# extruderControllerv03.net
KiCad netlist of a schematic drawn in EAGLE
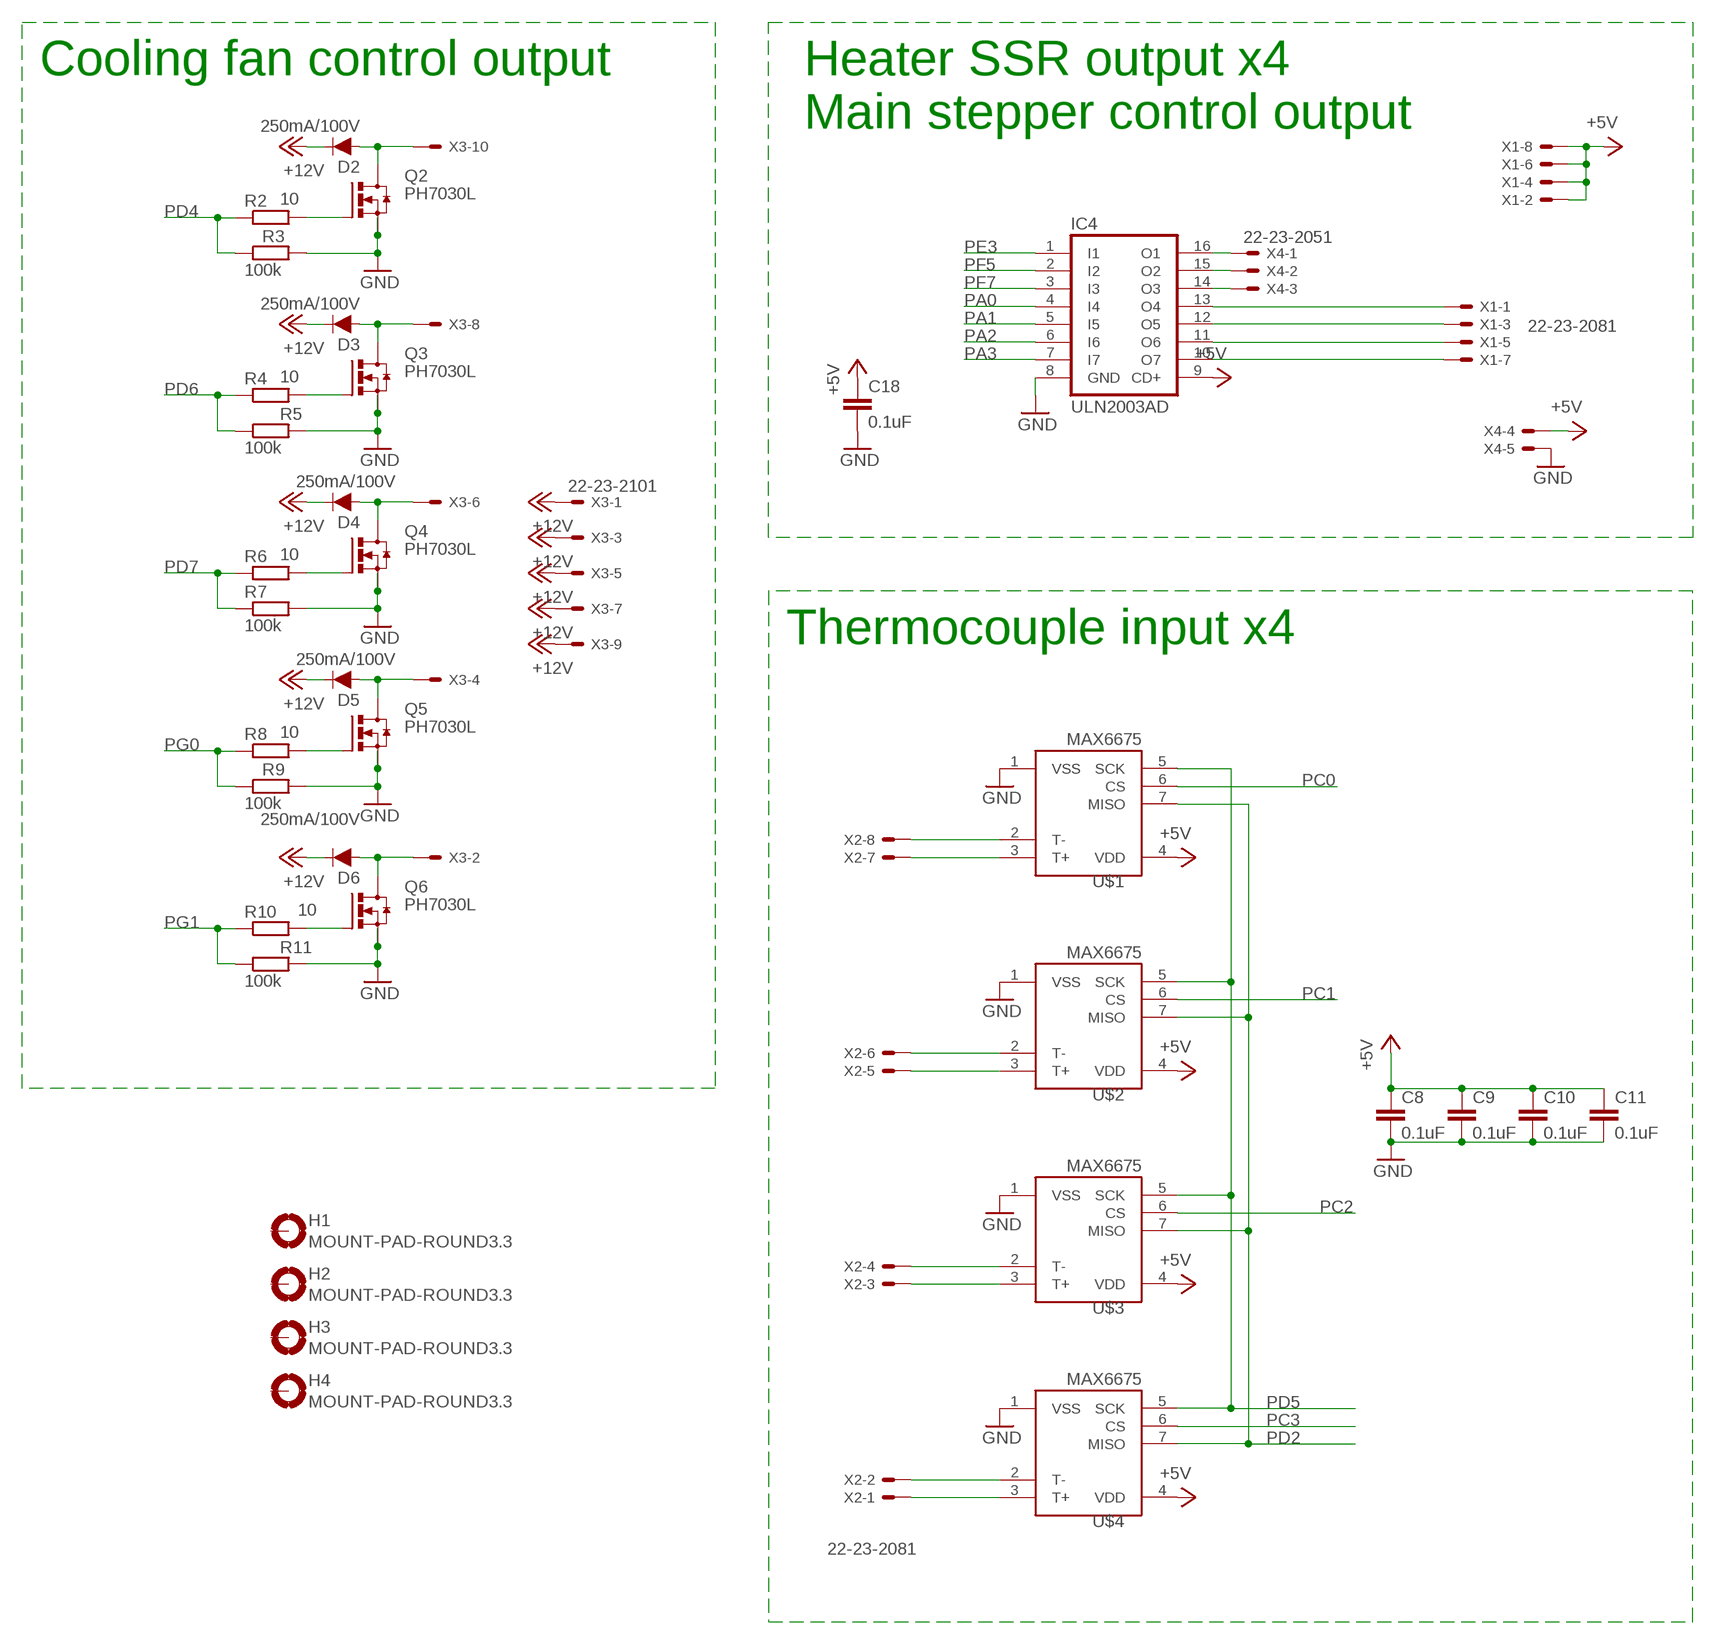
[diagram p0: schematic, sheet 1, part 1 of 2]
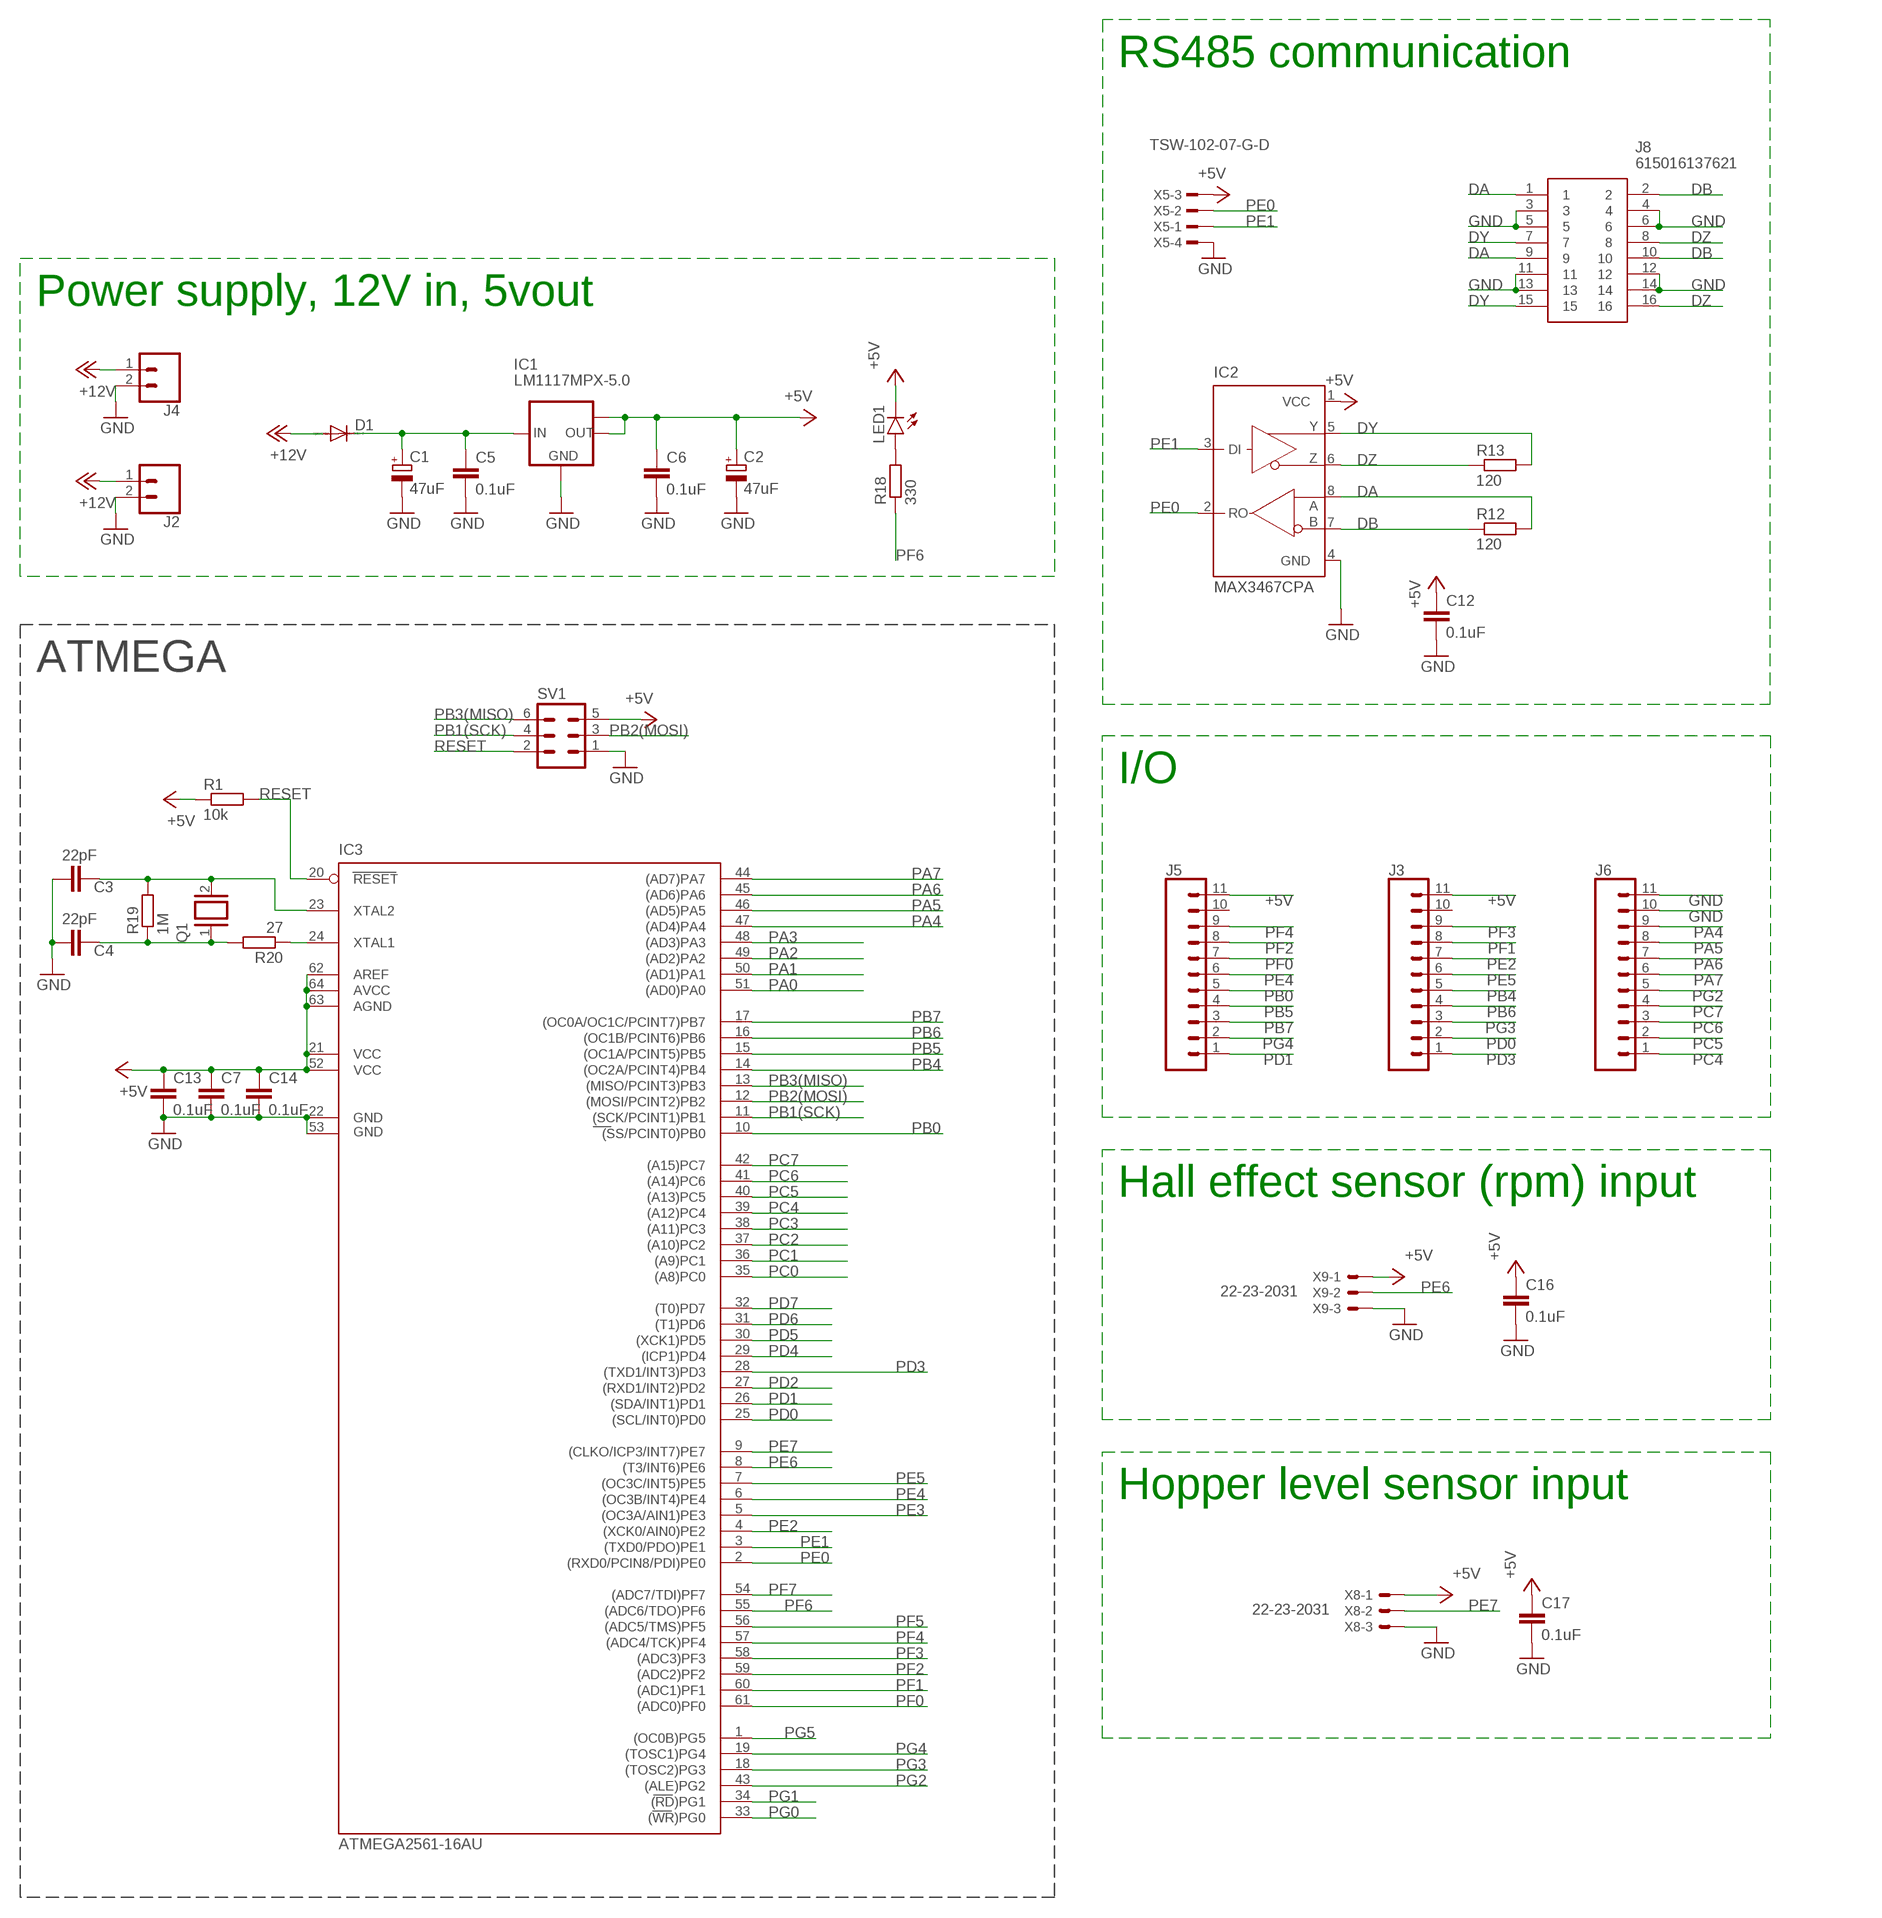
[diagram p1: schematic, sheet 1, part 2 of 2]

(export (version "E")
  (design (tool "Eeschema 10.0.6"))
  (components
    (comp (ref "C1")
      (value "47uF")
      (footprint "eagle-import:PANASONIC_D")
      (libsource (lib "eagle-import") (part "CPOL-EUD"))
    )
    (comp (ref "C2")
      (value "47uF")
      (footprint "eagle-import:PANASONIC_D")
      (libsource (lib "eagle-import") (part "CPOL-EUD"))
    )
    (comp (ref "C3")
      (value "22pF")
      (footprint "eagle-import:C0603")
      (libsource (lib "eagle-import") (part "C-EUC0603"))
    )
    (comp (ref "C4")
      (value "22pF")
      (footprint "eagle-import:C0603")
      (libsource (lib "eagle-import") (part "C-EUC0603"))
    )
    (comp (ref "C5")
      (value "0.1uF")
      (footprint "eagle-import:C0603")
      (libsource (lib "eagle-import") (part "C-EUC0603"))
    )
    (comp (ref "C6")
      (value "0.1uF")
      (footprint "eagle-import:C0603")
      (libsource (lib "eagle-import") (part "C-EUC0603"))
    )
    (comp (ref "C7")
      (value "0.1uF")
      (footprint "eagle-import:C0603")
      (libsource (lib "eagle-import") (part "C-EUC0603"))
    )
    (comp (ref "C8")
      (value "0.1uF")
      (footprint "eagle-import:C0603")
      (libsource (lib "eagle-import") (part "C-EUC0603"))
    )
    (comp (ref "C9")
      (value "0.1uF")
      (footprint "eagle-import:C0603")
      (libsource (lib "eagle-import") (part "C-EUC0603"))
    )
    (comp (ref "C10")
      (value "0.1uF")
      (footprint "eagle-import:C0603")
      (libsource (lib "eagle-import") (part "C-EUC0603"))
    )
    (comp (ref "C11")
      (value "0.1uF")
      (footprint "eagle-import:C0603")
      (libsource (lib "eagle-import") (part "C-EUC0603"))
    )
    (comp (ref "C12")
      (value "0.1uF")
      (footprint "eagle-import:C0603")
      (libsource (lib "eagle-import") (part "C-EUC0603"))
    )
    (comp (ref "C13")
      (value "0.1uF")
      (footprint "eagle-import:C0603")
      (libsource (lib "eagle-import") (part "C-EUC0603"))
    )
    (comp (ref "C14")
      (value "0.1uF")
      (footprint "eagle-import:C0603")
      (libsource (lib "eagle-import") (part "C-EUC0603"))
    )
    (comp (ref "C16")
      (value "0.1uF")
      (footprint "eagle-import:C0603")
      (libsource (lib "eagle-import") (part "C-EUC0603"))
    )
    (comp (ref "C17")
      (value "0.1uF")
      (footprint "eagle-import:C0603")
      (libsource (lib "eagle-import") (part "C-EUC0603"))
    )
    (comp (ref "C18")
      (value "0.1uF")
      (footprint "eagle-import:C0603")
      (libsource (lib "eagle-import") (part "C-EUC0603"))
    )
    (comp (ref "D1")
      (value "DIODE-SMB")
      (footprint "eagle-import:SMB")
      (libsource (lib "eagle-import") (part "DIODE-SMB"))
    )
    (comp (ref "D2")
      (value "250mA/100V")
      (footprint "eagle-import:SOD-323")
      (libsource (lib "eagle-import") (part "DIODE-BAS16J"))
    )
    (comp (ref "D3")
      (value "250mA/100V")
      (footprint "eagle-import:SOD-323")
      (libsource (lib "eagle-import") (part "DIODE-BAS16J"))
    )
    (comp (ref "D4")
      (value "250mA/100V")
      (footprint "eagle-import:SOD-323")
      (libsource (lib "eagle-import") (part "DIODE-BAS16J"))
    )
    (comp (ref "D5")
      (value "250mA/100V")
      (footprint "eagle-import:SOD-323")
      (libsource (lib "eagle-import") (part "DIODE-BAS16J"))
    )
    (comp (ref "D6")
      (value "250mA/100V")
      (footprint "eagle-import:SOD-323")
      (libsource (lib "eagle-import") (part "DIODE-BAS16J"))
    )
    (comp (ref "H1")
      (value "MOUNT-PAD-ROUND3.3")
      (footprint "eagle-import:3,3-PAD")
      (libsource (lib "eagle-import") (part "MOUNT-PAD-ROUND3.3"))
    )
    (comp (ref "H2")
      (value "MOUNT-PAD-ROUND3.3")
      (footprint "eagle-import:3,3-PAD")
      (libsource (lib "eagle-import") (part "MOUNT-PAD-ROUND3.3"))
    )
    (comp (ref "H3")
      (value "MOUNT-PAD-ROUND3.3")
      (footprint "eagle-import:3,3-PAD")
      (libsource (lib "eagle-import") (part "MOUNT-PAD-ROUND3.3"))
    )
    (comp (ref "H4")
      (value "MOUNT-PAD-ROUND3.3")
      (footprint "eagle-import:3,3-PAD")
      (libsource (lib "eagle-import") (part "MOUNT-PAD-ROUND3.3"))
    )
    (comp (ref "IC1")
      (value "LM1117MPX-5.0")
      (footprint "eagle-import:SOT223")
      (libsource (lib "eagle-import") (part "LM1117MPX-5.0"))
    )
    (comp (ref "IC2")
      (value "MAX3467CPA")
      (footprint "eagle-import:SO08")
      (libsource (lib "eagle-import") (part "MAX3467PAC"))
    )
    (comp (ref "IC3")
      (value "ATMEGA2561-16AU")
      (footprint "eagle-import:TQFP64")
      (libsource (lib "eagle-import") (part "ATMEGA2561AU-16"))
    )
    (comp (ref "IC4")
      (value "ULN2003AD")
      (footprint "eagle-import:SO16")
      (libsource (lib "eagle-import") (part "ULN2003AD"))
    )
    (comp (ref "J2")
      (value "CONN_023.5MM")
      (footprint "eagle-import:SCREWTERMINAL-3.5MM-2")
      (libsource (lib "eagle-import") (part "CONN_023.5MM"))
    )
    (comp (ref "J3")
      (value "CONN_11")
      (footprint "eagle-import:1X11")
      (libsource (lib "eagle-import") (part "CONN_11"))
    )
    (comp (ref "J4")
      (value "CONN_023.5MM")
      (footprint "eagle-import:SCREWTERMINAL-3.5MM-2")
      (libsource (lib "eagle-import") (part "CONN_023.5MM"))
    )
    (comp (ref "J5")
      (value "CONN_11")
      (footprint "eagle-import:1X11")
      (libsource (lib "eagle-import") (part "CONN_11"))
    )
    (comp (ref "J6")
      (value "CONN_11")
      (footprint "eagle-import:1X11")
      (libsource (lib "eagle-import") (part "CONN_11"))
    )
    (comp (ref "J8")
      (value "615016137621")
      (footprint "eagle-import:WR-MJ")
      (fields (field (name "MOUSER_PART_NUMBER") "710-615016137621"))
      (libsource (lib "eagle-import") (part "615016137621"))
    )
    (comp (ref "LED1")
      (value "LEDSML1206")
      (footprint "eagle-import:SML1206")
      (libsource (lib "eagle-import") (part "LEDSML1206"))
    )
    (comp (ref "Q1")
      (value "XTAL/S")
      (footprint "eagle-import:QS")
      (fields (field (name "SPICEPREFIX") "B"))
      (libsource (lib "eagle-import") (part "XTAL/S"))
    )
    (comp (ref "Q2")
      (value "PH7030L")
      (footprint "eagle-import:SOT669")
      (libsource (lib "eagle-import") (part "PH7030L"))
    )
    (comp (ref "Q3")
      (value "PH7030L")
      (footprint "eagle-import:SOT669")
      (libsource (lib "eagle-import") (part "PH7030L"))
    )
    (comp (ref "Q4")
      (value "PH7030L")
      (footprint "eagle-import:SOT669")
      (libsource (lib "eagle-import") (part "PH7030L"))
    )
    (comp (ref "Q5")
      (value "PH7030L")
      (footprint "eagle-import:SOT669")
      (libsource (lib "eagle-import") (part "PH7030L"))
    )
    (comp (ref "Q6")
      (value "PH7030L")
      (footprint "eagle-import:SOT669")
      (libsource (lib "eagle-import") (part "PH7030L"))
    )
    (comp (ref "R1")
      (value "10k")
      (footprint "eagle-import:R0805")
      (libsource (lib "eagle-import") (part "R-EU_R0805"))
    )
    (comp (ref "R2")
      (value "10")
      (footprint "eagle-import:R0805")
      (libsource (lib "eagle-import") (part "R-EU_R0805"))
    )
    (comp (ref "R3")
      (value "100k")
      (footprint "eagle-import:R0805")
      (libsource (lib "eagle-import") (part "R-EU_R0805"))
    )
    (comp (ref "R4")
      (value "10")
      (footprint "eagle-import:R0805")
      (libsource (lib "eagle-import") (part "R-EU_R0805"))
    )
    (comp (ref "R5")
      (value "100k")
      (footprint "eagle-import:R0805")
      (libsource (lib "eagle-import") (part "R-EU_R0805"))
    )
    (comp (ref "R6")
      (value "10")
      (footprint "eagle-import:R0805")
      (libsource (lib "eagle-import") (part "R-EU_R0805"))
    )
    (comp (ref "R7")
      (value "100k")
      (footprint "eagle-import:R0805")
      (libsource (lib "eagle-import") (part "R-EU_R0805"))
    )
    (comp (ref "R8")
      (value "10")
      (footprint "eagle-import:R0805")
      (libsource (lib "eagle-import") (part "R-EU_R0805"))
    )
    (comp (ref "R9")
      (value "100k")
      (footprint "eagle-import:R0805")
      (libsource (lib "eagle-import") (part "R-EU_R0805"))
    )
    (comp (ref "R10")
      (value "10")
      (footprint "eagle-import:R0805")
      (libsource (lib "eagle-import") (part "R-EU_R0805"))
    )
    (comp (ref "R11")
      (value "100k")
      (footprint "eagle-import:R0805")
      (libsource (lib "eagle-import") (part "R-EU_R0805"))
    )
    (comp (ref "R12")
      (value "120")
      (footprint "eagle-import:R1210")
      (libsource (lib "eagle-import") (part "R-EU_R1210"))
    )
    (comp (ref "R13")
      (value "120")
      (footprint "eagle-import:R1210")
      (libsource (lib "eagle-import") (part "R-EU_R1210"))
    )
    (comp (ref "R18")
      (value "330")
      (footprint "eagle-import:R0805")
      (libsource (lib "eagle-import") (part "R-EU_R0805"))
    )
    (comp (ref "R19")
      (value "1M")
      (footprint "eagle-import:R0805")
      (libsource (lib "eagle-import") (part "R-EU_R0805"))
    )
    (comp (ref "R20")
      (value "27")
      (footprint "eagle-import:R0805")
      (libsource (lib "eagle-import") (part "R-EU_R0805"))
    )
    (comp (ref "SV1")
      (value "MA03-2")
      (footprint "eagle-import:MA03-2")
      (libsource (lib "eagle-import") (part "MA03-2"))
    )
    (comp (ref "U$1")
      (value "MAX6675")
      (footprint "eagle-import:SO08-MAX6675")
      (libsource (lib "eagle-import") (part "MAX6675"))
    )
    (comp (ref "U$2")
      (value "MAX6675")
      (footprint "eagle-import:SO08-MAX6675")
      (libsource (lib "eagle-import") (part "MAX6675"))
    )
    (comp (ref "U$3")
      (value "MAX6675")
      (footprint "eagle-import:SO08-MAX6675")
      (libsource (lib "eagle-import") (part "MAX6675"))
    )
    (comp (ref "U$4")
      (value "MAX6675")
      (footprint "eagle-import:SO08-MAX6675")
      (libsource (lib "eagle-import") (part "MAX6675"))
    )
    (comp (ref "X1")
      (value "22-23-2081")
      (footprint "eagle-import:22-23-2081")
      (fields (field (name "MF") "MOLEX"))
      (libsource (lib "eagle-import") (part "22-23-2081"))
    )
    (comp (ref "X2")
      (value "22-23-2081")
      (footprint "eagle-import:22-23-2081")
      (fields (field (name "MF") "MOLEX"))
      (libsource (lib "eagle-import") (part "22-23-2081"))
    )
    (comp (ref "X3")
      (value "22-23-2101")
      (footprint "eagle-import:22-23-2101")
      (fields (field (name "MF") "MOLEX"))
      (libsource (lib "eagle-import") (part "22-23-2101"))
    )
    (comp (ref "X4")
      (value "22-23-2051")
      (footprint "eagle-import:22-23-2051")
      (fields (field (name "MF") "MOLEX"))
      (libsource (lib "eagle-import") (part "22-23-2051"))
    )
    (comp (ref "X5")
      (value "TSW-102-07-G-D")
      (footprint "eagle-import:TSW-102-XX-G-D")
      (fields (field (name "MF") "Samtec Inc."))
      (libsource (lib "eagle-import") (part "TSW-102--G-D07"))
    )
    (comp (ref "X8")
      (value "22-23-2031")
      (footprint "eagle-import:22-23-2031")
      (fields (field (name "MF") "MOLEX"))
      (libsource (lib "eagle-import") (part "22-23-2031"))
    )
    (comp (ref "X9")
      (value "22-23-2031")
      (footprint "eagle-import:22-23-2031")
      (fields (field (name "MF") "MOLEX"))
      (libsource (lib "eagle-import") (part "22-23-2031"))
    )
  )
  (nets
    (net (code "1") (name "+5V") (class "Default")
      (node (ref "C10") (pin "1") (pinfunction "1_1") (pintype "passive"))
      (node (ref "C11") (pin "1") (pinfunction "1_1") (pintype "passive"))
      (node (ref "C12") (pin "1") (pinfunction "1_1") (pintype "passive"))
      (node (ref "C13") (pin "1") (pinfunction "1_1") (pintype "passive"))
      (node (ref "C14") (pin "1") (pinfunction "1_1") (pintype "passive"))
      (node (ref "C16") (pin "1") (pinfunction "1_1") (pintype "passive"))
      (node (ref "C17") (pin "1") (pinfunction "1_1") (pintype "passive"))
      (node (ref "C18") (pin "1") (pinfunction "1_1") (pintype "passive"))
      (node (ref "C2") (pin "+") (pinfunction "+_+") (pintype "passive"))
      (node (ref "C6") (pin "1") (pinfunction "1_1") (pintype "passive"))
      (node (ref "C7") (pin "1") (pinfunction "1_1") (pintype "passive"))
      (node (ref "C8") (pin "1") (pinfunction "1_1") (pintype "passive"))
      (node (ref "C9") (pin "1") (pinfunction "1_1") (pintype "passive"))
      (node (ref "IC1") (pin "2") (pinfunction "OUT_2") (pintype "passive"))
      (node (ref "IC1") (pin "TAB") (pinfunction "OUT1_TAB") (pintype "passive"))
      (node (ref "IC2") (pin "1") (pinfunction "VCC_1") (pintype "power_in"))
      (node (ref "IC3") (pin "21") (pinfunction "VCC_21") (pintype "power_in"))
      (node (ref "IC3") (pin "52") (pinfunction "VCC1_52") (pintype "power_in"))
      (node (ref "IC3") (pin "62") (pinfunction "AREF_62") (pintype "bidirectional"))
      (node (ref "IC3") (pin "63") (pinfunction "AGND_63") (pintype "power_in"))
      (node (ref "IC3") (pin "64") (pinfunction "AVCC_64") (pintype "power_in"))
      (node (ref "IC4") (pin "9") (pinfunction "CD+_9") (pintype "passive"))
      (node (ref "J3") (pin "11") (pinfunction "11_11") (pintype "passive"))
      (node (ref "J5") (pin "11") (pinfunction "11_11") (pintype "passive"))
      (node (ref "LED1") (pin "C") (pinfunction "C_C") (pintype "passive"))
      (node (ref "R1") (pin "1") (pinfunction "1_1") (pintype "passive"))
      (node (ref "SV1") (pin "5") (pinfunction "5_5") (pintype "passive"))
      (node (ref "U$1") (pin "4") (pinfunction "VDD_4") (pintype "bidirectional"))
      (node (ref "U$2") (pin "4") (pinfunction "VDD_4") (pintype "bidirectional"))
      (node (ref "U$3") (pin "4") (pinfunction "VDD_4") (pintype "bidirectional"))
      (node (ref "U$4") (pin "4") (pinfunction "VDD_4") (pintype "bidirectional"))
      (node (ref "X1") (pin "2") (pinfunction "S_2") (pintype "passive"))
      (node (ref "X1") (pin "4") (pinfunction "S_4") (pintype "passive"))
      (node (ref "X1") (pin "6") (pinfunction "S_6") (pintype "passive"))
      (node (ref "X1") (pin "8") (pinfunction "S_8") (pintype "passive"))
      (node (ref "X4") (pin "4") (pinfunction "S_4") (pintype "passive"))
      (node (ref "X5") (pin "3") (pinfunction "1_3") (pintype "passive"))
      (node (ref "X8") (pin "1") (pinfunction "S_1") (pintype "passive"))
      (node (ref "X9") (pin "1") (pinfunction "S_1") (pintype "passive"))
    )
    (net (code "2") (name "+12V") (class "Default")
      (node (ref "D1") (pin "A") (pinfunction "A_A") (pintype "passive"))
      (node (ref "D2") (pin "C") (pinfunction "C_C") (pintype "passive"))
      (node (ref "D3") (pin "C") (pinfunction "C_C") (pintype "passive"))
      (node (ref "D4") (pin "C") (pinfunction "C_C") (pintype "passive"))
      (node (ref "D5") (pin "C") (pinfunction "C_C") (pintype "passive"))
      (node (ref "D6") (pin "C") (pinfunction "C_C") (pintype "passive"))
      (node (ref "J2") (pin "1") (pinfunction "1_1") (pintype "passive"))
      (node (ref "J4") (pin "1") (pinfunction "1_1") (pintype "passive"))
      (node (ref "X3") (pin "1") (pinfunction "S_1") (pintype "passive"))
      (node (ref "X3") (pin "3") (pinfunction "S_3") (pintype "passive"))
      (node (ref "X3") (pin "5") (pinfunction "S_5") (pintype "passive"))
      (node (ref "X3") (pin "7") (pinfunction "S_7") (pintype "passive"))
      (node (ref "X3") (pin "9") (pinfunction "S_9") (pintype "passive"))
    )
    (net (code "3") (name "/DA") (class "Default")
      (node (ref "IC2") (pin "8") (pinfunction "A_8") (pintype "passive"))
      (node (ref "J8") (pin "1") (pinfunction "1_1") (pintype "bidirectional"))
      (node (ref "J8") (pin "9") (pinfunction "9_9") (pintype "bidirectional"))
      (node (ref "R12") (pin "2") (pinfunction "2_2") (pintype "passive"))
    )
    (net (code "4") (name "/DB") (class "Default")
      (node (ref "IC2") (pin "7") (pinfunction "B_7") (pintype "passive"))
      (node (ref "J8") (pin "10") (pinfunction "10_10") (pintype "bidirectional"))
      (node (ref "J8") (pin "2") (pinfunction "2_2") (pintype "bidirectional"))
      (node (ref "R12") (pin "1") (pinfunction "1_1") (pintype "passive"))
    )
    (net (code "5") (name "/DY") (class "Default")
      (node (ref "IC2") (pin "5") (pinfunction "Y_5") (pintype "passive"))
      (node (ref "J8") (pin "15") (pinfunction "15_15") (pintype "bidirectional"))
      (node (ref "J8") (pin "7") (pinfunction "7_7") (pintype "bidirectional"))
      (node (ref "R13") (pin "2") (pinfunction "2_2") (pintype "passive"))
    )
    (net (code "6") (name "/DZ") (class "Default")
      (node (ref "IC2") (pin "6") (pinfunction "Z_6") (pintype "passive"))
      (node (ref "J8") (pin "16") (pinfunction "16_16") (pintype "bidirectional"))
      (node (ref "J8") (pin "8") (pinfunction "8_8") (pintype "bidirectional"))
      (node (ref "R13") (pin "1") (pinfunction "1_1") (pintype "passive"))
    )
    (net (code "7") (name "/PA0") (class "Default")
      (node (ref "IC3") (pin "51") (pinfunction "(AD0)PA0_51") (pintype "bidirectional"))
      (node (ref "IC4") (pin "4") (pinfunction "I4_4") (pintype "input"))
    )
    (net (code "8") (name "/PA1") (class "Default")
      (node (ref "IC3") (pin "50") (pinfunction "(AD1)PA1_50") (pintype "bidirectional"))
      (node (ref "IC4") (pin "5") (pinfunction "I5_5") (pintype "input"))
    )
    (net (code "9") (name "/PA2") (class "Default")
      (node (ref "IC3") (pin "49") (pinfunction "(AD2)PA2_49") (pintype "bidirectional"))
      (node (ref "IC4") (pin "6") (pinfunction "I6_6") (pintype "input"))
    )
    (net (code "10") (name "/PA3") (class "Default")
      (node (ref "IC3") (pin "48") (pinfunction "(AD3)PA3_48") (pintype "bidirectional"))
      (node (ref "IC4") (pin "7") (pinfunction "I7_7") (pintype "input"))
    )
    (net (code "11") (name "/PA4") (class "Default")
      (node (ref "IC3") (pin "47") (pinfunction "(AD4)PA4_47") (pintype "bidirectional"))
      (node (ref "J6") (pin "9") (pinfunction "9_9") (pintype "passive"))
    )
    (net (code "12") (name "/PA5") (class "Default")
      (node (ref "IC3") (pin "46") (pinfunction "(AD5)PA5_46") (pintype "bidirectional"))
      (node (ref "J6") (pin "8") (pinfunction "8_8") (pintype "passive"))
    )
    (net (code "13") (name "/PA6") (class "Default")
      (node (ref "IC3") (pin "45") (pinfunction "(AD6)PA6_45") (pintype "bidirectional"))
      (node (ref "J6") (pin "7") (pinfunction "7_7") (pintype "passive"))
    )
    (net (code "14") (name "/PA7") (class "Default")
      (node (ref "IC3") (pin "44") (pinfunction "(AD7)PA7_44") (pintype "bidirectional"))
      (node (ref "J6") (pin "6") (pinfunction "6_6") (pintype "passive"))
    )
    (net (code "15") (name "/PB0") (class "Default")
      (node (ref "IC3") (pin "10") (pinfunction "(SS/PCINT0)PB0_10") (pintype "bidirectional"))
      (node (ref "J5") (pin "5") (pinfunction "5_5") (pintype "passive"))
    )
    (net (code "16") (name "/PB1(SCK)") (class "Default")
      (node (ref "IC3") (pin "11") (pinfunction "(SCK/PCINT1)PB1_11") (pintype "bidirectional"))
      (node (ref "SV1") (pin "4") (pinfunction "4_4") (pintype "passive"))
    )
    (net (code "17") (name "/PB2(MOSI)") (class "Default")
      (node (ref "IC3") (pin "12") (pinfunction "(MOSI/PCINT2)PB2_12") (pintype "bidirectional"))
      (node (ref "SV1") (pin "3") (pinfunction "3_3") (pintype "passive"))
    )
    (net (code "18") (name "/PB3(MISO)") (class "Default")
      (node (ref "IC3") (pin "13") (pinfunction "(MISO/PCINT3)PB3_13") (pintype "bidirectional"))
      (node (ref "SV1") (pin "6") (pinfunction "6_6") (pintype "passive"))
    )
    (net (code "19") (name "/PB4") (class "Default")
      (node (ref "IC3") (pin "14") (pinfunction "(OC2A/PCINT4)PB4_14") (pintype "bidirectional"))
      (node (ref "J3") (pin "5") (pinfunction "5_5") (pintype "passive"))
    )
    (net (code "20") (name "/PB5") (class "Default")
      (node (ref "IC3") (pin "15") (pinfunction "(OC1A/PCINT5)PB5_15") (pintype "bidirectional"))
      (node (ref "J5") (pin "4") (pinfunction "4_4") (pintype "passive"))
    )
    (net (code "21") (name "/PB6") (class "Default")
      (node (ref "IC3") (pin "16") (pinfunction "(OC1B/PCINT6)PB6_16") (pintype "bidirectional"))
      (node (ref "J3") (pin "4") (pinfunction "4_4") (pintype "passive"))
    )
    (net (code "22") (name "/PB7") (class "Default")
      (node (ref "IC3") (pin "17") (pinfunction "(OC0A/OC1C/PCINT7)PB7_17") (pintype "bidirectional"))
      (node (ref "J5") (pin "3") (pinfunction "3_3") (pintype "passive"))
    )
    (net (code "23") (name "/PC0") (class "Default")
      (node (ref "IC3") (pin "35") (pinfunction "(A8)PC0_35") (pintype "bidirectional"))
      (node (ref "U$1") (pin "6") (pinfunction "CS_6") (pintype "bidirectional"))
    )
    (net (code "24") (name "/PC1") (class "Default")
      (node (ref "IC3") (pin "36") (pinfunction "(A9)PC1_36") (pintype "bidirectional"))
      (node (ref "U$2") (pin "6") (pinfunction "CS_6") (pintype "bidirectional"))
    )
    (net (code "25") (name "/PC2") (class "Default")
      (node (ref "IC3") (pin "37") (pinfunction "(A10)PC2_37") (pintype "bidirectional"))
      (node (ref "U$3") (pin "6") (pinfunction "CS_6") (pintype "bidirectional"))
    )
    (net (code "26") (name "/PC3") (class "Default")
      (node (ref "IC3") (pin "38") (pinfunction "(A11)PC3_38") (pintype "bidirectional"))
      (node (ref "U$4") (pin "6") (pinfunction "CS_6") (pintype "bidirectional"))
    )
    (net (code "27") (name "/PC4") (class "Default")
      (node (ref "IC3") (pin "39") (pinfunction "(A12)PC4_39") (pintype "bidirectional"))
      (node (ref "J6") (pin "1") (pinfunction "1_1") (pintype "passive"))
    )
    (net (code "28") (name "/PC5") (class "Default")
      (node (ref "IC3") (pin "40") (pinfunction "(A13)PC5_40") (pintype "bidirectional"))
      (node (ref "J6") (pin "2") (pinfunction "2_2") (pintype "passive"))
    )
    (net (code "29") (name "/PC6") (class "Default")
      (node (ref "IC3") (pin "41") (pinfunction "(A14)PC6_41") (pintype "bidirectional"))
      (node (ref "J6") (pin "3") (pinfunction "3_3") (pintype "passive"))
    )
    (net (code "30") (name "/PC7") (class "Default")
      (node (ref "IC3") (pin "42") (pinfunction "(A15)PC7_42") (pintype "bidirectional"))
      (node (ref "J6") (pin "4") (pinfunction "4_4") (pintype "passive"))
    )
    (net (code "31") (name "/PD0") (class "Default")
      (node (ref "IC3") (pin "25") (pinfunction "(SCL/INT0)PD0_25") (pintype "bidirectional"))
      (node (ref "J3") (pin "2") (pinfunction "2_2") (pintype "passive"))
    )
    (net (code "32") (name "/PD1") (class "Default")
      (node (ref "IC3") (pin "26") (pinfunction "(SDA/INT1)PD1_26") (pintype "bidirectional"))
      (node (ref "J5") (pin "1") (pinfunction "1_1") (pintype "passive"))
    )
    (net (code "33") (name "/PD2") (class "Default")
      (node (ref "IC3") (pin "27") (pinfunction "(RXD1/INT2)PD2_27") (pintype "bidirectional"))
      (node (ref "U$1") (pin "7") (pinfunction "MISO_7") (pintype "bidirectional"))
      (node (ref "U$2") (pin "7") (pinfunction "MISO_7") (pintype "bidirectional"))
      (node (ref "U$3") (pin "7") (pinfunction "MISO_7") (pintype "bidirectional"))
      (node (ref "U$4") (pin "7") (pinfunction "MISO_7") (pintype "bidirectional"))
    )
    (net (code "34") (name "/PD3") (class "Default")
      (node (ref "IC3") (pin "28") (pinfunction "(TXD1/INT3)PD3_28") (pintype "bidirectional"))
      (node (ref "J3") (pin "1") (pinfunction "1_1") (pintype "passive"))
    )
    (net (code "35") (name "/PD4") (class "Default")
      (node (ref "IC3") (pin "29") (pinfunction "(ICP1)PD4_29") (pintype "bidirectional"))
      (node (ref "R2") (pin "1") (pinfunction "1_1") (pintype "passive"))
      (node (ref "R3") (pin "1") (pinfunction "1_1") (pintype "passive"))
    )
    (net (code "36") (name "/PD5") (class "Default")
      (node (ref "IC3") (pin "30") (pinfunction "(XCK1)PD5_30") (pintype "bidirectional"))
      (node (ref "U$1") (pin "5") (pinfunction "SCK_5") (pintype "bidirectional"))
      (node (ref "U$2") (pin "5") (pinfunction "SCK_5") (pintype "bidirectional"))
      (node (ref "U$3") (pin "5") (pinfunction "SCK_5") (pintype "bidirectional"))
      (node (ref "U$4") (pin "5") (pinfunction "SCK_5") (pintype "bidirectional"))
    )
    (net (code "37") (name "/PD6") (class "Default")
      (node (ref "IC3") (pin "31") (pinfunction "(T1)PD6_31") (pintype "bidirectional"))
      (node (ref "R4") (pin "1") (pinfunction "1_1") (pintype "passive"))
      (node (ref "R5") (pin "1") (pinfunction "1_1") (pintype "passive"))
    )
    (net (code "38") (name "/PD7") (class "Default")
      (node (ref "IC3") (pin "32") (pinfunction "(T0)PD7_32") (pintype "bidirectional"))
      (node (ref "R6") (pin "1") (pinfunction "1_1") (pintype "passive"))
      (node (ref "R7") (pin "1") (pinfunction "1_1") (pintype "passive"))
    )
    (net (code "39") (name "/PE0") (class "Default")
      (node (ref "IC2") (pin "2") (pinfunction "RO_2") (pintype "output"))
      (node (ref "IC3") (pin "2") (pinfunction "(RXD0/PCIN8/PDI)PE0_2") (pintype "bidirectional"))
      (node (ref "X5") (pin "2") (pinfunction "1_2") (pintype "passive"))
    )
    (net (code "40") (name "/PE1") (class "Default")
      (node (ref "IC2") (pin "3") (pinfunction "DI_3") (pintype "input"))
      (node (ref "IC3") (pin "3") (pinfunction "(TXD0/PDO)PE1_3") (pintype "bidirectional"))
      (node (ref "X5") (pin "1") (pinfunction "1_1") (pintype "passive"))
    )
    (net (code "41") (name "/PE2") (class "Default")
      (node (ref "IC3") (pin "4") (pinfunction "(XCK0/AIN0)PE2_4") (pintype "bidirectional"))
      (node (ref "J3") (pin "7") (pinfunction "7_7") (pintype "passive"))
    )
    (net (code "42") (name "/PE3") (class "Default")
      (node (ref "IC3") (pin "5") (pinfunction "(OC3A/AIN1)PE3_5") (pintype "bidirectional"))
      (node (ref "IC4") (pin "1") (pinfunction "I1_1") (pintype "input"))
    )
    (net (code "43") (name "/PE4") (class "Default")
      (node (ref "IC3") (pin "6") (pinfunction "(OC3B/INT4)PE4_6") (pintype "bidirectional"))
      (node (ref "J5") (pin "6") (pinfunction "6_6") (pintype "passive"))
    )
    (net (code "44") (name "/PE5") (class "Default")
      (node (ref "IC3") (pin "7") (pinfunction "(OC3C/INT5)PE5_7") (pintype "bidirectional"))
      (node (ref "J3") (pin "6") (pinfunction "6_6") (pintype "passive"))
    )
    (net (code "45") (name "/PE6") (class "Default")
      (node (ref "IC3") (pin "8") (pinfunction "(T3/INT6)PE6_8") (pintype "bidirectional"))
      (node (ref "X9") (pin "2") (pinfunction "S_2") (pintype "passive"))
    )
    (net (code "46") (name "/PE7") (class "Default")
      (node (ref "IC3") (pin "9") (pinfunction "(CLKO/ICP3/INT7)PE7_9") (pintype "bidirectional"))
      (node (ref "X8") (pin "2") (pinfunction "S_2") (pintype "passive"))
    )
    (net (code "47") (name "/PF0") (class "Default")
      (node (ref "IC3") (pin "61") (pinfunction "(ADC0)PF0_61") (pintype "bidirectional"))
      (node (ref "J5") (pin "7") (pinfunction "7_7") (pintype "passive"))
    )
    (net (code "48") (name "/PF1") (class "Default")
      (node (ref "IC3") (pin "60") (pinfunction "(ADC1)PF1_60") (pintype "bidirectional"))
      (node (ref "J3") (pin "8") (pinfunction "8_8") (pintype "passive"))
    )
    (net (code "49") (name "/PF2") (class "Default")
      (node (ref "IC3") (pin "59") (pinfunction "(ADC2)PF2_59") (pintype "bidirectional"))
      (node (ref "J5") (pin "8") (pinfunction "8_8") (pintype "passive"))
    )
    (net (code "50") (name "/PF3") (class "Default")
      (node (ref "IC3") (pin "58") (pinfunction "(ADC3)PF3_58") (pintype "bidirectional"))
      (node (ref "J3") (pin "9") (pinfunction "9_9") (pintype "passive"))
    )
    (net (code "51") (name "/PF4") (class "Default")
      (node (ref "IC3") (pin "57") (pinfunction "(ADC4/TCK)PF4_57") (pintype "bidirectional"))
      (node (ref "J5") (pin "9") (pinfunction "9_9") (pintype "passive"))
    )
    (net (code "52") (name "/PF5") (class "Default")
      (node (ref "IC3") (pin "56") (pinfunction "(ADC5/TMS)PF5_56") (pintype "bidirectional"))
      (node (ref "IC4") (pin "2") (pinfunction "I2_2") (pintype "input"))
    )
    (net (code "53") (name "/PF6") (class "Default")
      (node (ref "IC3") (pin "55") (pinfunction "(ADC6/TDO)PF6_55") (pintype "bidirectional"))
      (node (ref "R18") (pin "1") (pinfunction "1_1") (pintype "passive"))
    )
    (net (code "54") (name "/PF7") (class "Default")
      (node (ref "IC3") (pin "54") (pinfunction "(ADC7/TDI)PF7_54") (pintype "bidirectional"))
      (node (ref "IC4") (pin "3") (pinfunction "I3_3") (pintype "input"))
    )
    (net (code "55") (name "/PG0") (class "Default")
      (node (ref "IC3") (pin "33") (pinfunction "(WR)PG0_33") (pintype "bidirectional"))
      (node (ref "R8") (pin "1") (pinfunction "1_1") (pintype "passive"))
      (node (ref "R9") (pin "1") (pinfunction "1_1") (pintype "passive"))
    )
    (net (code "56") (name "/PG1") (class "Default")
      (node (ref "IC3") (pin "34") (pinfunction "(RD)PG1_34") (pintype "bidirectional"))
      (node (ref "R10") (pin "1") (pinfunction "1_1") (pintype "passive"))
      (node (ref "R11") (pin "1") (pinfunction "1_1") (pintype "passive"))
    )
    (net (code "57") (name "/PG2") (class "Default")
      (node (ref "IC3") (pin "43") (pinfunction "(ALE)PG2_43") (pintype "bidirectional"))
      (node (ref "J6") (pin "5") (pinfunction "5_5") (pintype "passive"))
    )
    (net (code "58") (name "/PG3") (class "Default")
      (node (ref "IC3") (pin "18") (pinfunction "(TOSC2)PG3_18") (pintype "bidirectional"))
      (node (ref "J3") (pin "3") (pinfunction "3_3") (pintype "passive"))
    )
    (net (code "59") (name "/PG4") (class "Default")
      (node (ref "IC3") (pin "19") (pinfunction "(TOSC1)PG4_19") (pintype "bidirectional"))
      (node (ref "J5") (pin "2") (pinfunction "2_2") (pintype "passive"))
    )
    (net (code "60") (name "/PG5") (class "Default")
      (node (ref "IC3") (pin "1") (pinfunction "(OC0B)PG5_1") (pintype "bidirectional"))
    )
    (net (code "61") (name "/RESET") (class "Default")
      (node (ref "IC3") (pin "20") (pinfunction "RESET_20") (pintype "input"))
      (node (ref "R1") (pin "2") (pinfunction "2_2") (pintype "passive"))
      (node (ref "SV1") (pin "2") (pinfunction "2_2") (pintype "passive"))
    )
    (net (code "62") (name "GND") (class "Default")
      (node (ref "C1") (pin "-") (pinfunction "-_-") (pintype "passive"))
      (node (ref "C10") (pin "2") (pinfunction "2_2") (pintype "passive"))
      (node (ref "C11") (pin "2") (pinfunction "2_2") (pintype "passive"))
      (node (ref "C12") (pin "2") (pinfunction "2_2") (pintype "passive"))
      (node (ref "C13") (pin "2") (pinfunction "2_2") (pintype "passive"))
      (node (ref "C14") (pin "2") (pinfunction "2_2") (pintype "passive"))
      (node (ref "C16") (pin "2") (pinfunction "2_2") (pintype "passive"))
      (node (ref "C17") (pin "2") (pinfunction "2_2") (pintype "passive"))
      (node (ref "C18") (pin "2") (pinfunction "2_2") (pintype "passive"))
      (node (ref "C2") (pin "-") (pinfunction "-_-") (pintype "passive"))
      (node (ref "C3") (pin "2") (pinfunction "2_2") (pintype "passive"))
      (node (ref "C4") (pin "2") (pinfunction "2_2") (pintype "passive"))
      (node (ref "C5") (pin "2") (pinfunction "2_2") (pintype "passive"))
      (node (ref "C6") (pin "2") (pinfunction "2_2") (pintype "passive"))
      (node (ref "C7") (pin "2") (pinfunction "2_2") (pintype "passive"))
      (node (ref "C8") (pin "2") (pinfunction "2_2") (pintype "passive"))
      (node (ref "C9") (pin "2") (pinfunction "2_2") (pintype "passive"))
      (node (ref "IC1") (pin "1") (pinfunction "GND_1") (pintype "input"))
      (node (ref "IC2") (pin "4") (pinfunction "GND_4") (pintype "power_in"))
      (node (ref "IC3") (pin "22") (pinfunction "GND_22") (pintype "power_in"))
      (node (ref "IC3") (pin "53") (pinfunction "GND1_53") (pintype "power_in"))
      (node (ref "IC4") (pin "8") (pinfunction "GND_8") (pintype "power_in"))
      (node (ref "J2") (pin "2") (pinfunction "2_2") (pintype "passive"))
      (node (ref "J4") (pin "2") (pinfunction "2_2") (pintype "passive"))
      (node (ref "J6") (pin "10") (pinfunction "10_10") (pintype "passive"))
      (node (ref "J6") (pin "11") (pinfunction "11_11") (pintype "passive"))
      (node (ref "J8") (pin "11") (pinfunction "11_11") (pintype "bidirectional"))
      (node (ref "J8") (pin "12") (pinfunction "12_12") (pintype "bidirectional"))
      (node (ref "J8") (pin "13") (pinfunction "13_13") (pintype "bidirectional"))
      (node (ref "J8") (pin "14") (pinfunction "14_14") (pintype "bidirectional"))
      (node (ref "J8") (pin "3") (pinfunction "3_3") (pintype "bidirectional"))
      (node (ref "J8") (pin "4") (pinfunction "4_4") (pintype "bidirectional"))
      (node (ref "J8") (pin "5") (pinfunction "5_5") (pintype "bidirectional"))
      (node (ref "J8") (pin "6") (pinfunction "6_6") (pintype "bidirectional"))
      (node (ref "Q2") (pin "1") (pinfunction "S_1") (pintype "passive"))
      (node (ref "Q2") (pin "2") (pinfunction "S_2") (pintype "passive"))
      (node (ref "Q2") (pin "3") (pinfunction "S_3") (pintype "passive"))
      (node (ref "Q3") (pin "1") (pinfunction "S_1") (pintype "passive"))
      (node (ref "Q3") (pin "2") (pinfunction "S_2") (pintype "passive"))
      (node (ref "Q3") (pin "3") (pinfunction "S_3") (pintype "passive"))
      (node (ref "Q4") (pin "1") (pinfunction "S_1") (pintype "passive"))
      (node (ref "Q4") (pin "2") (pinfunction "S_2") (pintype "passive"))
      (node (ref "Q4") (pin "3") (pinfunction "S_3") (pintype "passive"))
      (node (ref "Q5") (pin "1") (pinfunction "S_1") (pintype "passive"))
      (node (ref "Q5") (pin "2") (pinfunction "S_2") (pintype "passive"))
      (node (ref "Q5") (pin "3") (pinfunction "S_3") (pintype "passive"))
      (node (ref "Q6") (pin "1") (pinfunction "S_1") (pintype "passive"))
      (node (ref "Q6") (pin "2") (pinfunction "S_2") (pintype "passive"))
      (node (ref "Q6") (pin "3") (pinfunction "S_3") (pintype "passive"))
      (node (ref "R11") (pin "2") (pinfunction "2_2") (pintype "passive"))
      (node (ref "R3") (pin "2") (pinfunction "2_2") (pintype "passive"))
      (node (ref "R5") (pin "2") (pinfunction "2_2") (pintype "passive"))
      (node (ref "R7") (pin "2") (pinfunction "2_2") (pintype "passive"))
      (node (ref "R9") (pin "2") (pinfunction "2_2") (pintype "passive"))
      (node (ref "SV1") (pin "1") (pinfunction "1_1") (pintype "passive"))
      (node (ref "U$1") (pin "1") (pinfunction "VSS_1") (pintype "bidirectional"))
      (node (ref "U$2") (pin "1") (pinfunction "VSS_1") (pintype "bidirectional"))
      (node (ref "U$3") (pin "1") (pinfunction "VSS_1") (pintype "bidirectional"))
      (node (ref "U$4") (pin "1") (pinfunction "VSS_1") (pintype "bidirectional"))
      (node (ref "X4") (pin "5") (pinfunction "S_5") (pintype "passive"))
      (node (ref "X5") (pin "4") (pinfunction "1_4") (pintype "passive"))
      (node (ref "X8") (pin "3") (pinfunction "S_3") (pintype "passive"))
      (node (ref "X9") (pin "3") (pinfunction "S_3") (pintype "passive"))
    )
    (net (code "63") (name "Net-(C4-Pad1)") (class "Default")
      (node (ref "C4") (pin "1") (pinfunction "1_1") (pintype "passive"))
      (node (ref "Q1") (pin "1") (pinfunction "1_1") (pintype "passive"))
      (node (ref "R19") (pin "1") (pinfunction "1_1") (pintype "passive"))
      (node (ref "R20") (pin "2") (pinfunction "2_2") (pintype "passive"))
    )
    (net (code "64") (name "Net-(IC1-IN)") (class "Default")
      (node (ref "C1") (pin "+") (pinfunction "+_+") (pintype "passive"))
      (node (ref "C5") (pin "1") (pinfunction "1_1") (pintype "passive"))
      (node (ref "D1") (pin "C") (pinfunction "C_C") (pintype "passive"))
      (node (ref "IC1") (pin "3") (pinfunction "IN_3") (pintype "input"))
    )
    (net (code "65") (name "Net-(IC3-XTAL1)") (class "Default")
      (node (ref "IC3") (pin "24") (pinfunction "XTAL1_24") (pintype "input"))
      (node (ref "R20") (pin "1") (pinfunction "1_1") (pintype "passive"))
    )
    (net (code "66") (name "Net-(IC3-XTAL2)") (class "Default")
      (node (ref "C3") (pin "1") (pinfunction "1_1") (pintype "passive"))
      (node (ref "IC3") (pin "23") (pinfunction "XTAL2_23") (pintype "output"))
      (node (ref "Q1") (pin "2") (pinfunction "2_2") (pintype "passive"))
      (node (ref "R19") (pin "2") (pinfunction "2_2") (pintype "passive"))
    )
    (net (code "67") (name "Net-(IC4-O1)") (class "Default")
      (node (ref "IC4") (pin "16") (pinfunction "O1_16") (pintype "open_collector"))
      (node (ref "X4") (pin "1") (pinfunction "S_1") (pintype "passive"))
    )
    (net (code "68") (name "Net-(IC4-O2)") (class "Default")
      (node (ref "IC4") (pin "15") (pinfunction "O2_15") (pintype "open_collector"))
      (node (ref "X4") (pin "2") (pinfunction "S_2") (pintype "passive"))
    )
    (net (code "69") (name "Net-(IC4-O3)") (class "Default")
      (node (ref "IC4") (pin "14") (pinfunction "O3_14") (pintype "open_collector"))
      (node (ref "X4") (pin "3") (pinfunction "S_3") (pintype "passive"))
    )
    (net (code "70") (name "Net-(IC4-O4)") (class "Default")
      (node (ref "IC4") (pin "13") (pinfunction "O4_13") (pintype "open_collector"))
      (node (ref "X1") (pin "1") (pinfunction "S_1") (pintype "passive"))
    )
    (net (code "71") (name "Net-(IC4-O5)") (class "Default")
      (node (ref "IC4") (pin "12") (pinfunction "O5_12") (pintype "open_collector"))
      (node (ref "X1") (pin "3") (pinfunction "S_3") (pintype "passive"))
    )
    (net (code "72") (name "Net-(IC4-O6)") (class "Default")
      (node (ref "IC4") (pin "11") (pinfunction "O6_11") (pintype "open_collector"))
      (node (ref "X1") (pin "5") (pinfunction "S_5") (pintype "passive"))
    )
    (net (code "73") (name "Net-(IC4-O7)") (class "Default")
      (node (ref "IC4") (pin "10") (pinfunction "O7_10") (pintype "open_collector"))
      (node (ref "X1") (pin "7") (pinfunction "S_7") (pintype "passive"))
    )
    (net (code "74") (name "Net-(LED1-PadA)") (class "Default")
      (node (ref "LED1") (pin "A") (pinfunction "A_A") (pintype "passive"))
      (node (ref "R18") (pin "2") (pinfunction "2_2") (pintype "passive"))
    )
    (net (code "75") (name "Net-(Q2-D)") (class "Default")
      (node (ref "D2") (pin "A") (pinfunction "A_A") (pintype "passive"))
      (node (ref "Q2") (pin "MB") (pinfunction "D_MB") (pintype "passive"))
      (node (ref "X3") (pin "10") (pinfunction "S_10") (pintype "passive"))
    )
    (net (code "76") (name "Net-(Q2-G)") (class "Default")
      (node (ref "Q2") (pin "4") (pinfunction "G_4") (pintype "passive"))
      (node (ref "R2") (pin "2") (pinfunction "2_2") (pintype "passive"))
    )
    (net (code "77") (name "Net-(Q3-D)") (class "Default")
      (node (ref "D3") (pin "A") (pinfunction "A_A") (pintype "passive"))
      (node (ref "Q3") (pin "MB") (pinfunction "D_MB") (pintype "passive"))
      (node (ref "X3") (pin "8") (pinfunction "S_8") (pintype "passive"))
    )
    (net (code "78") (name "Net-(Q3-G)") (class "Default")
      (node (ref "Q3") (pin "4") (pinfunction "G_4") (pintype "passive"))
      (node (ref "R4") (pin "2") (pinfunction "2_2") (pintype "passive"))
    )
    (net (code "79") (name "Net-(Q4-D)") (class "Default")
      (node (ref "D4") (pin "A") (pinfunction "A_A") (pintype "passive"))
      (node (ref "Q4") (pin "MB") (pinfunction "D_MB") (pintype "passive"))
      (node (ref "X3") (pin "6") (pinfunction "S_6") (pintype "passive"))
    )
    (net (code "80") (name "Net-(Q4-G)") (class "Default")
      (node (ref "Q4") (pin "4") (pinfunction "G_4") (pintype "passive"))
      (node (ref "R6") (pin "2") (pinfunction "2_2") (pintype "passive"))
    )
    (net (code "81") (name "Net-(Q5-D)") (class "Default")
      (node (ref "D5") (pin "A") (pinfunction "A_A") (pintype "passive"))
      (node (ref "Q5") (pin "MB") (pinfunction "D_MB") (pintype "passive"))
      (node (ref "X3") (pin "4") (pinfunction "S_4") (pintype "passive"))
    )
    (net (code "82") (name "Net-(Q5-G)") (class "Default")
      (node (ref "Q5") (pin "4") (pinfunction "G_4") (pintype "passive"))
      (node (ref "R8") (pin "2") (pinfunction "2_2") (pintype "passive"))
    )
    (net (code "83") (name "Net-(Q6-D)") (class "Default")
      (node (ref "D6") (pin "A") (pinfunction "A_A") (pintype "passive"))
      (node (ref "Q6") (pin "MB") (pinfunction "D_MB") (pintype "passive"))
      (node (ref "X3") (pin "2") (pinfunction "S_2") (pintype "passive"))
    )
    (net (code "84") (name "Net-(Q6-G)") (class "Default")
      (node (ref "Q6") (pin "4") (pinfunction "G_4") (pintype "passive"))
      (node (ref "R10") (pin "2") (pinfunction "2_2") (pintype "passive"))
    )
    (net (code "85") (name "Net-(U$1-T+)") (class "Default")
      (node (ref "U$1") (pin "3") (pinfunction "T+_3") (pintype "bidirectional"))
      (node (ref "X2") (pin "7") (pinfunction "S_7") (pintype "passive"))
    )
    (net (code "86") (name "Net-(U$1-T-)") (class "Default")
      (node (ref "U$1") (pin "2") (pinfunction "T-_2") (pintype "bidirectional"))
      (node (ref "X2") (pin "8") (pinfunction "S_8") (pintype "passive"))
    )
    (net (code "87") (name "Net-(U$2-T+)") (class "Default")
      (node (ref "U$2") (pin "3") (pinfunction "T+_3") (pintype "bidirectional"))
      (node (ref "X2") (pin "5") (pinfunction "S_5") (pintype "passive"))
    )
    (net (code "88") (name "Net-(U$2-T-)") (class "Default")
      (node (ref "U$2") (pin "2") (pinfunction "T-_2") (pintype "bidirectional"))
      (node (ref "X2") (pin "6") (pinfunction "S_6") (pintype "passive"))
    )
    (net (code "89") (name "Net-(U$3-T+)") (class "Default")
      (node (ref "U$3") (pin "3") (pinfunction "T+_3") (pintype "bidirectional"))
      (node (ref "X2") (pin "3") (pinfunction "S_3") (pintype "passive"))
    )
    (net (code "90") (name "Net-(U$3-T-)") (class "Default")
      (node (ref "U$3") (pin "2") (pinfunction "T-_2") (pintype "bidirectional"))
      (node (ref "X2") (pin "4") (pinfunction "S_4") (pintype "passive"))
    )
    (net (code "91") (name "Net-(U$4-T+)") (class "Default")
      (node (ref "U$4") (pin "3") (pinfunction "T+_3") (pintype "bidirectional"))
      (node (ref "X2") (pin "1") (pinfunction "S_1") (pintype "passive"))
    )
    (net (code "92") (name "Net-(U$4-T-)") (class "Default")
      (node (ref "U$4") (pin "2") (pinfunction "T-_2") (pintype "bidirectional"))
      (node (ref "X2") (pin "2") (pinfunction "S_2") (pintype "passive"))
    )
    (net (code "93") (name "unconnected-(H1-MOUNT-PadB3,3)") (class "Default")
      (node (ref "H1") (pin "B3,3") (pinfunction "MOUNT_B3,3") (pintype "passive"))
    )
    (net (code "94") (name "unconnected-(H2-MOUNT-PadB3,3)") (class "Default")
      (node (ref "H2") (pin "B3,3") (pinfunction "MOUNT_B3,3") (pintype "passive"))
    )
    (net (code "95") (name "unconnected-(H3-MOUNT-PadB3,3)") (class "Default")
      (node (ref "H3") (pin "B3,3") (pinfunction "MOUNT_B3,3") (pintype "passive"))
    )
    (net (code "96") (name "unconnected-(H4-MOUNT-PadB3,3)") (class "Default")
      (node (ref "H4") (pin "B3,3") (pinfunction "MOUNT_B3,3") (pintype "passive"))
    )
    (net (code "97") (name "unconnected-(J3-Pad10)") (class "Default")
      (node (ref "J3") (pin "10") (pinfunction "10_10") (pintype "passive"))
    )
    (net (code "98") (name "unconnected-(J5-Pad10)") (class "Default")
      (node (ref "J5") (pin "10") (pinfunction "10_10") (pintype "passive"))
    )
  )
)
